# Nusbio_-_Ex_Bread_Board.net
KiCad netlist of a schematic drawn in EAGLE
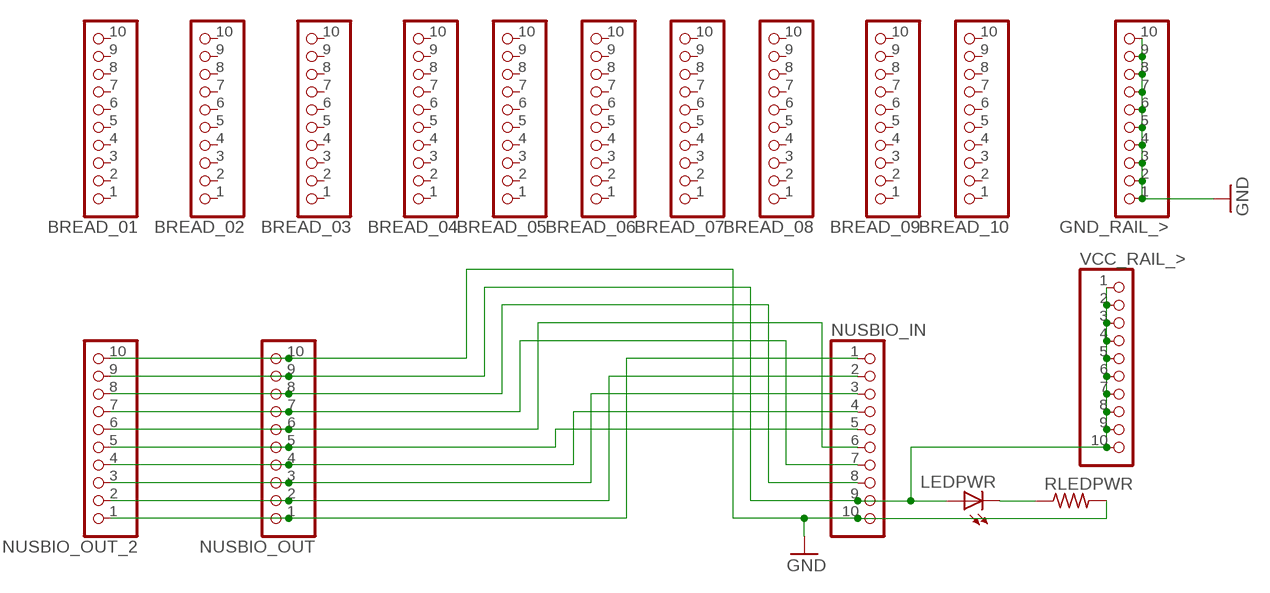
[diagram p0: schematic, sheet 1]

(export (version "E")
  (design (tool "Eeschema 10.0.6"))
  (components
    (comp (ref "BREAD_01")
      (value "PINHD-1X10")
      (footprint "eagle-import:1X10-BIG")
      (libsource (lib "eagle-import") (part "PINHD-1X10"))
    )
    (comp (ref "BREAD_02")
      (value "PINHD-1X10")
      (footprint "eagle-import:1X10-BIG")
      (libsource (lib "eagle-import") (part "PINHD-1X10"))
    )
    (comp (ref "BREAD_03")
      (value "PINHD-1X10")
      (footprint "eagle-import:1X10-BIG")
      (libsource (lib "eagle-import") (part "PINHD-1X10"))
    )
    (comp (ref "BREAD_04")
      (value "PINHD-1X10")
      (footprint "eagle-import:1X10-BIG")
      (libsource (lib "eagle-import") (part "PINHD-1X10"))
    )
    (comp (ref "BREAD_05")
      (value "PINHD-1X10")
      (footprint "eagle-import:1X10-BIG")
      (libsource (lib "eagle-import") (part "PINHD-1X10"))
    )
    (comp (ref "BREAD_06")
      (value "PINHD-1X10")
      (footprint "eagle-import:1X10-BIG")
      (libsource (lib "eagle-import") (part "PINHD-1X10"))
    )
    (comp (ref "BREAD_07")
      (value "PINHD-1X10")
      (footprint "eagle-import:1X10-BIG")
      (libsource (lib "eagle-import") (part "PINHD-1X10"))
    )
    (comp (ref "BREAD_08")
      (value "PINHD-1X10")
      (footprint "eagle-import:1X10-BIG")
      (libsource (lib "eagle-import") (part "PINHD-1X10"))
    )
    (comp (ref "BREAD_09")
      (value "PINHD-1X10")
      (footprint "eagle-import:1X10-BIG")
      (libsource (lib "eagle-import") (part "PINHD-1X10"))
    )
    (comp (ref "BREAD_10")
      (value "PINHD-1X10")
      (footprint "eagle-import:1X10-BIG")
      (libsource (lib "eagle-import") (part "PINHD-1X10"))
    )
    (comp (ref "GND_RAIL_>")
      (value "PINHD-1X10")
      (footprint "eagle-import:1X10-BIG")
      (libsource (lib "eagle-import") (part "PINHD-1X10"))
    )
    (comp (ref "LEDPWR")
      (value "LEDCHIPLED_0805")
      (footprint "eagle-import:CHIPLED_0805")
      (libsource (lib "eagle-import") (part "LEDCHIPLED_0805"))
    )
    (comp (ref "NUSBIO_IN")
      (value "PINHD-1X10")
      (footprint "eagle-import:1X10-BIG")
      (libsource (lib "eagle-import") (part "PINHD-1X10"))
    )
    (comp (ref "NUSBIO_OUT")
      (value "PINHD-1X10")
      (footprint "eagle-import:1X10-BIG")
      (libsource (lib "eagle-import") (part "PINHD-1X10"))
    )
    (comp (ref "NUSBIO_OUT_2")
      (value "PINHD-1X10")
      (footprint "eagle-import:1X10-BIG")
      (libsource (lib "eagle-import") (part "PINHD-1X10"))
    )
    (comp (ref "RLEDPWR")
      (value "R-US_R0805")
      (footprint "eagle-import:R0805")
      (libsource (lib "eagle-import") (part "R-US_R0805"))
    )
    (comp (ref "VCC_RAIL_>")
      (value "PINHD-1X10")
      (footprint "eagle-import:1X10-BIG")
      (libsource (lib "eagle-import") (part "PINHD-1X10"))
    )
  )
  (nets
    (net (code "1") (name "GND") (class "Default")
      (node (ref "GND_RAIL_>") (pin "1") (pinfunction "1_1") (pintype "passive"))
      (node (ref "GND_RAIL_>") (pin "10") (pinfunction "10_10") (pintype "passive"))
      (node (ref "GND_RAIL_>") (pin "2") (pinfunction "2_2") (pintype "passive"))
      (node (ref "GND_RAIL_>") (pin "3") (pinfunction "3_3") (pintype "passive"))
      (node (ref "GND_RAIL_>") (pin "4") (pinfunction "4_4") (pintype "passive"))
      (node (ref "GND_RAIL_>") (pin "5") (pinfunction "5_5") (pintype "passive"))
      (node (ref "GND_RAIL_>") (pin "6") (pinfunction "6_6") (pintype "passive"))
      (node (ref "GND_RAIL_>") (pin "7") (pinfunction "7_7") (pintype "passive"))
      (node (ref "GND_RAIL_>") (pin "8") (pinfunction "8_8") (pintype "passive"))
      (node (ref "GND_RAIL_>") (pin "9") (pinfunction "9_9") (pintype "passive"))
      (node (ref "NUSBIO_IN") (pin "10") (pinfunction "10_10") (pintype "passive"))
      (node (ref "NUSBIO_OUT") (pin "10") (pinfunction "10_10") (pintype "passive"))
      (node (ref "NUSBIO_OUT_2") (pin "10") (pinfunction "10_10") (pintype "passive"))
      (node (ref "RLEDPWR") (pin "2") (pinfunction "2_2") (pintype "passive"))
    )
    (net (code "2") (name "Net-(LEDPWR-PadA)") (class "Default")
      (node (ref "LEDPWR") (pin "A") (pinfunction "A_A") (pintype "passive"))
      (node (ref "NUSBIO_IN") (pin "9") (pinfunction "9_9") (pintype "passive"))
      (node (ref "NUSBIO_OUT") (pin "9") (pinfunction "9_9") (pintype "passive"))
      (node (ref "NUSBIO_OUT_2") (pin "9") (pinfunction "9_9") (pintype "passive"))
      (node (ref "VCC_RAIL_>") (pin "1") (pinfunction "1_1") (pintype "passive"))
      (node (ref "VCC_RAIL_>") (pin "10") (pinfunction "10_10") (pintype "passive"))
      (node (ref "VCC_RAIL_>") (pin "2") (pinfunction "2_2") (pintype "passive"))
      (node (ref "VCC_RAIL_>") (pin "3") (pinfunction "3_3") (pintype "passive"))
      (node (ref "VCC_RAIL_>") (pin "4") (pinfunction "4_4") (pintype "passive"))
      (node (ref "VCC_RAIL_>") (pin "5") (pinfunction "5_5") (pintype "passive"))
      (node (ref "VCC_RAIL_>") (pin "6") (pinfunction "6_6") (pintype "passive"))
      (node (ref "VCC_RAIL_>") (pin "7") (pinfunction "7_7") (pintype "passive"))
      (node (ref "VCC_RAIL_>") (pin "8") (pinfunction "8_8") (pintype "passive"))
      (node (ref "VCC_RAIL_>") (pin "9") (pinfunction "9_9") (pintype "passive"))
    )
    (net (code "3") (name "Net-(LEDPWR-PadC)") (class "Default")
      (node (ref "LEDPWR") (pin "C") (pinfunction "C_C") (pintype "passive"))
      (node (ref "RLEDPWR") (pin "1") (pinfunction "1_1") (pintype "passive"))
    )
    (net (code "4") (name "Net-(NUSBIO_IN-Pad1)") (class "Default")
      (node (ref "NUSBIO_IN") (pin "1") (pinfunction "1_1") (pintype "passive"))
      (node (ref "NUSBIO_OUT") (pin "1") (pinfunction "1_1") (pintype "passive"))
      (node (ref "NUSBIO_OUT_2") (pin "1") (pinfunction "1_1") (pintype "passive"))
    )
    (net (code "5") (name "Net-(NUSBIO_IN-Pad2)") (class "Default")
      (node (ref "NUSBIO_IN") (pin "2") (pinfunction "2_2") (pintype "passive"))
      (node (ref "NUSBIO_OUT") (pin "2") (pinfunction "2_2") (pintype "passive"))
      (node (ref "NUSBIO_OUT_2") (pin "2") (pinfunction "2_2") (pintype "passive"))
    )
    (net (code "6") (name "Net-(NUSBIO_IN-Pad3)") (class "Default")
      (node (ref "NUSBIO_IN") (pin "3") (pinfunction "3_3") (pintype "passive"))
      (node (ref "NUSBIO_OUT") (pin "3") (pinfunction "3_3") (pintype "passive"))
      (node (ref "NUSBIO_OUT_2") (pin "3") (pinfunction "3_3") (pintype "passive"))
    )
    (net (code "7") (name "Net-(NUSBIO_IN-Pad4)") (class "Default")
      (node (ref "NUSBIO_IN") (pin "4") (pinfunction "4_4") (pintype "passive"))
      (node (ref "NUSBIO_OUT") (pin "4") (pinfunction "4_4") (pintype "passive"))
      (node (ref "NUSBIO_OUT_2") (pin "4") (pinfunction "4_4") (pintype "passive"))
    )
    (net (code "8") (name "Net-(NUSBIO_IN-Pad5)") (class "Default")
      (node (ref "NUSBIO_IN") (pin "5") (pinfunction "5_5") (pintype "passive"))
      (node (ref "NUSBIO_OUT") (pin "5") (pinfunction "5_5") (pintype "passive"))
      (node (ref "NUSBIO_OUT_2") (pin "5") (pinfunction "5_5") (pintype "passive"))
    )
    (net (code "9") (name "Net-(NUSBIO_IN-Pad6)") (class "Default")
      (node (ref "NUSBIO_IN") (pin "6") (pinfunction "6_6") (pintype "passive"))
      (node (ref "NUSBIO_OUT") (pin "6") (pinfunction "6_6") (pintype "passive"))
      (node (ref "NUSBIO_OUT_2") (pin "6") (pinfunction "6_6") (pintype "passive"))
    )
    (net (code "10") (name "Net-(NUSBIO_IN-Pad7)") (class "Default")
      (node (ref "NUSBIO_IN") (pin "7") (pinfunction "7_7") (pintype "passive"))
      (node (ref "NUSBIO_OUT") (pin "7") (pinfunction "7_7") (pintype "passive"))
      (node (ref "NUSBIO_OUT_2") (pin "7") (pinfunction "7_7") (pintype "passive"))
    )
    (net (code "11") (name "Net-(NUSBIO_IN-Pad8)") (class "Default")
      (node (ref "NUSBIO_IN") (pin "8") (pinfunction "8_8") (pintype "passive"))
      (node (ref "NUSBIO_OUT") (pin "8") (pinfunction "8_8") (pintype "passive"))
      (node (ref "NUSBIO_OUT_2") (pin "8") (pinfunction "8_8") (pintype "passive"))
    )
    (net (code "12") (name "unconnected-(BREAD_01-Pad1)") (class "Default")
      (node (ref "BREAD_01") (pin "1") (pinfunction "1_1") (pintype "passive"))
    )
    (net (code "13") (name "unconnected-(BREAD_01-Pad2)") (class "Default")
      (node (ref "BREAD_01") (pin "2") (pinfunction "2_2") (pintype "passive"))
    )
    (net (code "14") (name "unconnected-(BREAD_01-Pad3)") (class "Default")
      (node (ref "BREAD_01") (pin "3") (pinfunction "3_3") (pintype "passive"))
    )
    (net (code "15") (name "unconnected-(BREAD_01-Pad4)") (class "Default")
      (node (ref "BREAD_01") (pin "4") (pinfunction "4_4") (pintype "passive"))
    )
    (net (code "16") (name "unconnected-(BREAD_01-Pad5)") (class "Default")
      (node (ref "BREAD_01") (pin "5") (pinfunction "5_5") (pintype "passive"))
    )
    (net (code "17") (name "unconnected-(BREAD_01-Pad6)") (class "Default")
      (node (ref "BREAD_01") (pin "6") (pinfunction "6_6") (pintype "passive"))
    )
    (net (code "18") (name "unconnected-(BREAD_01-Pad7)") (class "Default")
      (node (ref "BREAD_01") (pin "7") (pinfunction "7_7") (pintype "passive"))
    )
    (net (code "19") (name "unconnected-(BREAD_01-Pad8)") (class "Default")
      (node (ref "BREAD_01") (pin "8") (pinfunction "8_8") (pintype "passive"))
    )
    (net (code "20") (name "unconnected-(BREAD_01-Pad9)") (class "Default")
      (node (ref "BREAD_01") (pin "9") (pinfunction "9_9") (pintype "passive"))
    )
    (net (code "21") (name "unconnected-(BREAD_01-Pad10)") (class "Default")
      (node (ref "BREAD_01") (pin "10") (pinfunction "10_10") (pintype "passive"))
    )
    (net (code "22") (name "unconnected-(BREAD_02-Pad1)") (class "Default")
      (node (ref "BREAD_02") (pin "1") (pinfunction "1_1") (pintype "passive"))
    )
    (net (code "23") (name "unconnected-(BREAD_02-Pad2)") (class "Default")
      (node (ref "BREAD_02") (pin "2") (pinfunction "2_2") (pintype "passive"))
    )
    (net (code "24") (name "unconnected-(BREAD_02-Pad3)") (class "Default")
      (node (ref "BREAD_02") (pin "3") (pinfunction "3_3") (pintype "passive"))
    )
    (net (code "25") (name "unconnected-(BREAD_02-Pad4)") (class "Default")
      (node (ref "BREAD_02") (pin "4") (pinfunction "4_4") (pintype "passive"))
    )
    (net (code "26") (name "unconnected-(BREAD_02-Pad5)") (class "Default")
      (node (ref "BREAD_02") (pin "5") (pinfunction "5_5") (pintype "passive"))
    )
    (net (code "27") (name "unconnected-(BREAD_02-Pad6)") (class "Default")
      (node (ref "BREAD_02") (pin "6") (pinfunction "6_6") (pintype "passive"))
    )
    (net (code "28") (name "unconnected-(BREAD_02-Pad7)") (class "Default")
      (node (ref "BREAD_02") (pin "7") (pinfunction "7_7") (pintype "passive"))
    )
    (net (code "29") (name "unconnected-(BREAD_02-Pad8)") (class "Default")
      (node (ref "BREAD_02") (pin "8") (pinfunction "8_8") (pintype "passive"))
    )
    (net (code "30") (name "unconnected-(BREAD_02-Pad9)") (class "Default")
      (node (ref "BREAD_02") (pin "9") (pinfunction "9_9") (pintype "passive"))
    )
    (net (code "31") (name "unconnected-(BREAD_02-Pad10)") (class "Default")
      (node (ref "BREAD_02") (pin "10") (pinfunction "10_10") (pintype "passive"))
    )
    (net (code "32") (name "unconnected-(BREAD_03-Pad1)") (class "Default")
      (node (ref "BREAD_03") (pin "1") (pinfunction "1_1") (pintype "passive"))
    )
    (net (code "33") (name "unconnected-(BREAD_03-Pad2)") (class "Default")
      (node (ref "BREAD_03") (pin "2") (pinfunction "2_2") (pintype "passive"))
    )
    (net (code "34") (name "unconnected-(BREAD_03-Pad3)") (class "Default")
      (node (ref "BREAD_03") (pin "3") (pinfunction "3_3") (pintype "passive"))
    )
    (net (code "35") (name "unconnected-(BREAD_03-Pad4)") (class "Default")
      (node (ref "BREAD_03") (pin "4") (pinfunction "4_4") (pintype "passive"))
    )
    (net (code "36") (name "unconnected-(BREAD_03-Pad5)") (class "Default")
      (node (ref "BREAD_03") (pin "5") (pinfunction "5_5") (pintype "passive"))
    )
    (net (code "37") (name "unconnected-(BREAD_03-Pad6)") (class "Default")
      (node (ref "BREAD_03") (pin "6") (pinfunction "6_6") (pintype "passive"))
    )
    (net (code "38") (name "unconnected-(BREAD_03-Pad7)") (class "Default")
      (node (ref "BREAD_03") (pin "7") (pinfunction "7_7") (pintype "passive"))
    )
    (net (code "39") (name "unconnected-(BREAD_03-Pad8)") (class "Default")
      (node (ref "BREAD_03") (pin "8") (pinfunction "8_8") (pintype "passive"))
    )
    (net (code "40") (name "unconnected-(BREAD_03-Pad9)") (class "Default")
      (node (ref "BREAD_03") (pin "9") (pinfunction "9_9") (pintype "passive"))
    )
    (net (code "41") (name "unconnected-(BREAD_03-Pad10)") (class "Default")
      (node (ref "BREAD_03") (pin "10") (pinfunction "10_10") (pintype "passive"))
    )
    (net (code "42") (name "unconnected-(BREAD_04-Pad1)") (class "Default")
      (node (ref "BREAD_04") (pin "1") (pinfunction "1_1") (pintype "passive"))
    )
    (net (code "43") (name "unconnected-(BREAD_04-Pad2)") (class "Default")
      (node (ref "BREAD_04") (pin "2") (pinfunction "2_2") (pintype "passive"))
    )
    (net (code "44") (name "unconnected-(BREAD_04-Pad3)") (class "Default")
      (node (ref "BREAD_04") (pin "3") (pinfunction "3_3") (pintype "passive"))
    )
    (net (code "45") (name "unconnected-(BREAD_04-Pad4)") (class "Default")
      (node (ref "BREAD_04") (pin "4") (pinfunction "4_4") (pintype "passive"))
    )
    (net (code "46") (name "unconnected-(BREAD_04-Pad5)") (class "Default")
      (node (ref "BREAD_04") (pin "5") (pinfunction "5_5") (pintype "passive"))
    )
    (net (code "47") (name "unconnected-(BREAD_04-Pad6)") (class "Default")
      (node (ref "BREAD_04") (pin "6") (pinfunction "6_6") (pintype "passive"))
    )
    (net (code "48") (name "unconnected-(BREAD_04-Pad7)") (class "Default")
      (node (ref "BREAD_04") (pin "7") (pinfunction "7_7") (pintype "passive"))
    )
    (net (code "49") (name "unconnected-(BREAD_04-Pad8)") (class "Default")
      (node (ref "BREAD_04") (pin "8") (pinfunction "8_8") (pintype "passive"))
    )
    (net (code "50") (name "unconnected-(BREAD_04-Pad9)") (class "Default")
      (node (ref "BREAD_04") (pin "9") (pinfunction "9_9") (pintype "passive"))
    )
    (net (code "51") (name "unconnected-(BREAD_04-Pad10)") (class "Default")
      (node (ref "BREAD_04") (pin "10") (pinfunction "10_10") (pintype "passive"))
    )
    (net (code "52") (name "unconnected-(BREAD_05-Pad1)") (class "Default")
      (node (ref "BREAD_05") (pin "1") (pinfunction "1_1") (pintype "passive"))
    )
    (net (code "53") (name "unconnected-(BREAD_05-Pad2)") (class "Default")
      (node (ref "BREAD_05") (pin "2") (pinfunction "2_2") (pintype "passive"))
    )
    (net (code "54") (name "unconnected-(BREAD_05-Pad3)") (class "Default")
      (node (ref "BREAD_05") (pin "3") (pinfunction "3_3") (pintype "passive"))
    )
    (net (code "55") (name "unconnected-(BREAD_05-Pad4)") (class "Default")
      (node (ref "BREAD_05") (pin "4") (pinfunction "4_4") (pintype "passive"))
    )
    (net (code "56") (name "unconnected-(BREAD_05-Pad5)") (class "Default")
      (node (ref "BREAD_05") (pin "5") (pinfunction "5_5") (pintype "passive"))
    )
    (net (code "57") (name "unconnected-(BREAD_05-Pad6)") (class "Default")
      (node (ref "BREAD_05") (pin "6") (pinfunction "6_6") (pintype "passive"))
    )
    (net (code "58") (name "unconnected-(BREAD_05-Pad7)") (class "Default")
      (node (ref "BREAD_05") (pin "7") (pinfunction "7_7") (pintype "passive"))
    )
    (net (code "59") (name "unconnected-(BREAD_05-Pad8)") (class "Default")
      (node (ref "BREAD_05") (pin "8") (pinfunction "8_8") (pintype "passive"))
    )
    (net (code "60") (name "unconnected-(BREAD_05-Pad9)") (class "Default")
      (node (ref "BREAD_05") (pin "9") (pinfunction "9_9") (pintype "passive"))
    )
    (net (code "61") (name "unconnected-(BREAD_05-Pad10)") (class "Default")
      (node (ref "BREAD_05") (pin "10") (pinfunction "10_10") (pintype "passive"))
    )
    (net (code "62") (name "unconnected-(BREAD_06-Pad1)") (class "Default")
      (node (ref "BREAD_06") (pin "1") (pinfunction "1_1") (pintype "passive"))
    )
    (net (code "63") (name "unconnected-(BREAD_06-Pad2)") (class "Default")
      (node (ref "BREAD_06") (pin "2") (pinfunction "2_2") (pintype "passive"))
    )
    (net (code "64") (name "unconnected-(BREAD_06-Pad3)") (class "Default")
      (node (ref "BREAD_06") (pin "3") (pinfunction "3_3") (pintype "passive"))
    )
    (net (code "65") (name "unconnected-(BREAD_06-Pad4)") (class "Default")
      (node (ref "BREAD_06") (pin "4") (pinfunction "4_4") (pintype "passive"))
    )
    (net (code "66") (name "unconnected-(BREAD_06-Pad5)") (class "Default")
      (node (ref "BREAD_06") (pin "5") (pinfunction "5_5") (pintype "passive"))
    )
    (net (code "67") (name "unconnected-(BREAD_06-Pad6)") (class "Default")
      (node (ref "BREAD_06") (pin "6") (pinfunction "6_6") (pintype "passive"))
    )
    (net (code "68") (name "unconnected-(BREAD_06-Pad7)") (class "Default")
      (node (ref "BREAD_06") (pin "7") (pinfunction "7_7") (pintype "passive"))
    )
    (net (code "69") (name "unconnected-(BREAD_06-Pad8)") (class "Default")
      (node (ref "BREAD_06") (pin "8") (pinfunction "8_8") (pintype "passive"))
    )
    (net (code "70") (name "unconnected-(BREAD_06-Pad9)") (class "Default")
      (node (ref "BREAD_06") (pin "9") (pinfunction "9_9") (pintype "passive"))
    )
    (net (code "71") (name "unconnected-(BREAD_06-Pad10)") (class "Default")
      (node (ref "BREAD_06") (pin "10") (pinfunction "10_10") (pintype "passive"))
    )
    (net (code "72") (name "unconnected-(BREAD_07-Pad1)") (class "Default")
      (node (ref "BREAD_07") (pin "1") (pinfunction "1_1") (pintype "passive"))
    )
    (net (code "73") (name "unconnected-(BREAD_07-Pad2)") (class "Default")
      (node (ref "BREAD_07") (pin "2") (pinfunction "2_2") (pintype "passive"))
    )
    (net (code "74") (name "unconnected-(BREAD_07-Pad3)") (class "Default")
      (node (ref "BREAD_07") (pin "3") (pinfunction "3_3") (pintype "passive"))
    )
    (net (code "75") (name "unconnected-(BREAD_07-Pad4)") (class "Default")
      (node (ref "BREAD_07") (pin "4") (pinfunction "4_4") (pintype "passive"))
    )
    (net (code "76") (name "unconnected-(BREAD_07-Pad5)") (class "Default")
      (node (ref "BREAD_07") (pin "5") (pinfunction "5_5") (pintype "passive"))
    )
    (net (code "77") (name "unconnected-(BREAD_07-Pad6)") (class "Default")
      (node (ref "BREAD_07") (pin "6") (pinfunction "6_6") (pintype "passive"))
    )
    (net (code "78") (name "unconnected-(BREAD_07-Pad7)") (class "Default")
      (node (ref "BREAD_07") (pin "7") (pinfunction "7_7") (pintype "passive"))
    )
    (net (code "79") (name "unconnected-(BREAD_07-Pad8)") (class "Default")
      (node (ref "BREAD_07") (pin "8") (pinfunction "8_8") (pintype "passive"))
    )
    (net (code "80") (name "unconnected-(BREAD_07-Pad9)") (class "Default")
      (node (ref "BREAD_07") (pin "9") (pinfunction "9_9") (pintype "passive"))
    )
    (net (code "81") (name "unconnected-(BREAD_07-Pad10)") (class "Default")
      (node (ref "BREAD_07") (pin "10") (pinfunction "10_10") (pintype "passive"))
    )
    (net (code "82") (name "unconnected-(BREAD_08-Pad1)") (class "Default")
      (node (ref "BREAD_08") (pin "1") (pinfunction "1_1") (pintype "passive"))
    )
    (net (code "83") (name "unconnected-(BREAD_08-Pad2)") (class "Default")
      (node (ref "BREAD_08") (pin "2") (pinfunction "2_2") (pintype "passive"))
    )
    (net (code "84") (name "unconnected-(BREAD_08-Pad3)") (class "Default")
      (node (ref "BREAD_08") (pin "3") (pinfunction "3_3") (pintype "passive"))
    )
    (net (code "85") (name "unconnected-(BREAD_08-Pad4)") (class "Default")
      (node (ref "BREAD_08") (pin "4") (pinfunction "4_4") (pintype "passive"))
    )
    (net (code "86") (name "unconnected-(BREAD_08-Pad5)") (class "Default")
      (node (ref "BREAD_08") (pin "5") (pinfunction "5_5") (pintype "passive"))
    )
    (net (code "87") (name "unconnected-(BREAD_08-Pad6)") (class "Default")
      (node (ref "BREAD_08") (pin "6") (pinfunction "6_6") (pintype "passive"))
    )
    (net (code "88") (name "unconnected-(BREAD_08-Pad7)") (class "Default")
      (node (ref "BREAD_08") (pin "7") (pinfunction "7_7") (pintype "passive"))
    )
    (net (code "89") (name "unconnected-(BREAD_08-Pad8)") (class "Default")
      (node (ref "BREAD_08") (pin "8") (pinfunction "8_8") (pintype "passive"))
    )
    (net (code "90") (name "unconnected-(BREAD_08-Pad9)") (class "Default")
      (node (ref "BREAD_08") (pin "9") (pinfunction "9_9") (pintype "passive"))
    )
    (net (code "91") (name "unconnected-(BREAD_08-Pad10)") (class "Default")
      (node (ref "BREAD_08") (pin "10") (pinfunction "10_10") (pintype "passive"))
    )
    (net (code "92") (name "unconnected-(BREAD_09-Pad1)") (class "Default")
      (node (ref "BREAD_09") (pin "1") (pinfunction "1_1") (pintype "passive"))
    )
    (net (code "93") (name "unconnected-(BREAD_09-Pad2)") (class "Default")
      (node (ref "BREAD_09") (pin "2") (pinfunction "2_2") (pintype "passive"))
    )
    (net (code "94") (name "unconnected-(BREAD_09-Pad3)") (class "Default")
      (node (ref "BREAD_09") (pin "3") (pinfunction "3_3") (pintype "passive"))
    )
    (net (code "95") (name "unconnected-(BREAD_09-Pad4)") (class "Default")
      (node (ref "BREAD_09") (pin "4") (pinfunction "4_4") (pintype "passive"))
    )
    (net (code "96") (name "unconnected-(BREAD_09-Pad5)") (class "Default")
      (node (ref "BREAD_09") (pin "5") (pinfunction "5_5") (pintype "passive"))
    )
    (net (code "97") (name "unconnected-(BREAD_09-Pad6)") (class "Default")
      (node (ref "BREAD_09") (pin "6") (pinfunction "6_6") (pintype "passive"))
    )
    (net (code "98") (name "unconnected-(BREAD_09-Pad7)") (class "Default")
      (node (ref "BREAD_09") (pin "7") (pinfunction "7_7") (pintype "passive"))
    )
    (net (code "99") (name "unconnected-(BREAD_09-Pad8)") (class "Default")
      (node (ref "BREAD_09") (pin "8") (pinfunction "8_8") (pintype "passive"))
    )
    (net (code "100") (name "unconnected-(BREAD_09-Pad9)") (class "Default")
      (node (ref "BREAD_09") (pin "9") (pinfunction "9_9") (pintype "passive"))
    )
    (net (code "101") (name "unconnected-(BREAD_09-Pad10)") (class "Default")
      (node (ref "BREAD_09") (pin "10") (pinfunction "10_10") (pintype "passive"))
    )
    (net (code "102") (name "unconnected-(BREAD_10-Pad1)") (class "Default")
      (node (ref "BREAD_10") (pin "1") (pinfunction "1_1") (pintype "passive"))
    )
    (net (code "103") (name "unconnected-(BREAD_10-Pad2)") (class "Default")
      (node (ref "BREAD_10") (pin "2") (pinfunction "2_2") (pintype "passive"))
    )
    (net (code "104") (name "unconnected-(BREAD_10-Pad3)") (class "Default")
      (node (ref "BREAD_10") (pin "3") (pinfunction "3_3") (pintype "passive"))
    )
    (net (code "105") (name "unconnected-(BREAD_10-Pad4)") (class "Default")
      (node (ref "BREAD_10") (pin "4") (pinfunction "4_4") (pintype "passive"))
    )
    (net (code "106") (name "unconnected-(BREAD_10-Pad5)") (class "Default")
      (node (ref "BREAD_10") (pin "5") (pinfunction "5_5") (pintype "passive"))
    )
    (net (code "107") (name "unconnected-(BREAD_10-Pad6)") (class "Default")
      (node (ref "BREAD_10") (pin "6") (pinfunction "6_6") (pintype "passive"))
    )
    (net (code "108") (name "unconnected-(BREAD_10-Pad7)") (class "Default")
      (node (ref "BREAD_10") (pin "7") (pinfunction "7_7") (pintype "passive"))
    )
    (net (code "109") (name "unconnected-(BREAD_10-Pad8)") (class "Default")
      (node (ref "BREAD_10") (pin "8") (pinfunction "8_8") (pintype "passive"))
    )
    (net (code "110") (name "unconnected-(BREAD_10-Pad9)") (class "Default")
      (node (ref "BREAD_10") (pin "9") (pinfunction "9_9") (pintype "passive"))
    )
    (net (code "111") (name "unconnected-(BREAD_10-Pad10)") (class "Default")
      (node (ref "BREAD_10") (pin "10") (pinfunction "10_10") (pintype "passive"))
    )
  )
)
